# 06_ETHERNET.net
KiCad netlist of a schematic drawn in Altium Designer
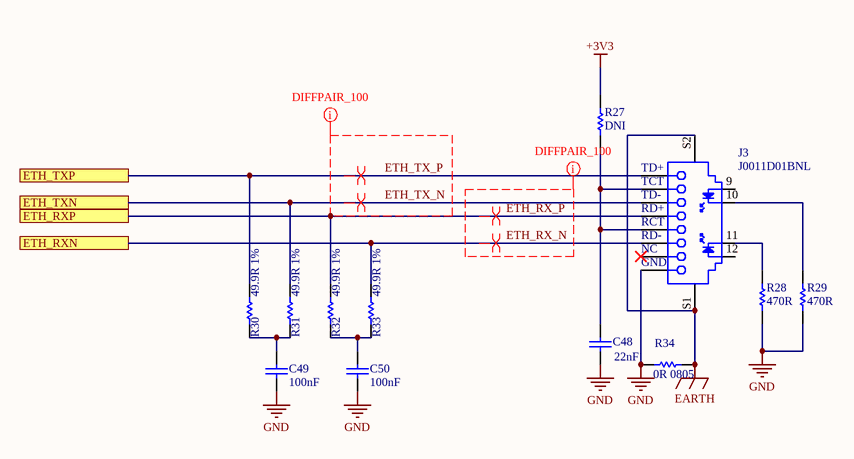
[diagram p0: 06. ETHERNET.SchDoc]

(export (version "E")
  (design (tool "Eeschema 10.0.6"))
  (components
    (comp (ref "C48")
      (value "22nF")
      (footprint "CAPC1005X60X30LL05T10")
      (fields (field (name "PART NUMBER") "GRM155R71H223KA12D") (field (name "MANUFACTURER") "Murata"))
      (libsource (lib "AM3358_DEV_BOARD") (part "CAP"))
    )
    (comp (ref "C49")
      (value "100nF")
      (footprint "CAPC1005X60X30LL05T10")
      (description "Chip Capacitor, 0.1 uF, +/- 10%, 16 V, -55 to 125 degC, 0402 (1005 Metric), RoHS, Tape and Reel")
      (fields (field (name "VOLTAGE") "16V") (field (name "TOLERANCE") "10%"))
      (libsource (lib "AM3358_DEV_BOARD") (part "CAP-NP-2"))
    )
    (comp (ref "C50")
      (value "100nF")
      (footprint "CAPC1005X60X30LL05T10")
      (description "Chip Capacitor, 0.1 uF, +/- 10%, 16 V, -55 to 125 degC, 0402 (1005 Metric), RoHS, Tape and Reel")
      (fields (field (name "VOLTAGE") "16V") (field (name "TOLERANCE") "10%"))
      (libsource (lib "AM3358_DEV_BOARD") (part "CAP-NP-2"))
    )
    (comp (ref "J3")
      (value "J0011D01BNL")
      (footprint "J0011D01BNL 1PORT 100 BASE-TX")
      (fields (field (name "MANUFACTURER") "Pulse Electronics"))
      (libsource (lib "AM3358_DEV_BOARD") (part "RJ45-12-2SHLD_F"))
    )
    (comp (ref "R27")
      (value "DNI")
      (footprint "RESC1005X40X25LL05T05")
      (fields (field (name "PART NUMBER") "CRCW040210R0FKEDHP") (field (name "MANUFACTURER") "Vishay Dale"))
      (libsource (lib "AM3358_DEV_BOARD") (part "RES"))
    )
    (comp (ref "R28")
      (value "470R")
      (footprint "RESC1005X40X25LL05T05")
      (fields (field (name "PART NUMBER") "CRCW0603470RFKEA") (field (name "MANUFACTURER") "Vishay Dale"))
      (libsource (lib "AM3358_DEV_BOARD") (part "RES"))
    )
    (comp (ref "R29")
      (value "470R")
      (footprint "RESC1005X40X25LL05T05")
      (fields (field (name "PART NUMBER") "CRCW0603470RFKEA") (field (name "MANUFACTURER") "Vishay Dale"))
      (libsource (lib "AM3358_DEV_BOARD") (part "RES"))
    )
    (comp (ref "R30")
      (value "49.9R 1%")
      (footprint "RESC1005X40X25LL05T05")
      (description "Precision Thick Film Chip Resistors")
      (fields (field (name "MANUFACTURER") "Panasonic") (field (name "PART NUMBER") "ERJ-2RKF49R9X"))
      (libsource (lib "AM3358_DEV_BOARD") (part "RES"))
    )
    (comp (ref "R31")
      (value "49.9R 1%")
      (footprint "RESC1005X40X25LL05T05")
      (description "Precision Thick Film Chip Resistors")
      (fields (field (name "MANUFACTURER") "Panasonic") (field (name "PART NUMBER") "ERJ-2RKF49R9X"))
      (libsource (lib "AM3358_DEV_BOARD") (part "RES"))
    )
    (comp (ref "R32")
      (value "49.9R 1%")
      (footprint "RESC1005X40X25LL05T05")
      (description "Precision Thick Film Chip Resistors")
      (fields (field (name "MANUFACTURER") "Panasonic") (field (name "PART NUMBER") "ERJ-2RKF49R9X"))
      (libsource (lib "AM3358_DEV_BOARD") (part "RES"))
    )
    (comp (ref "R33")
      (value "49.9R 1%")
      (footprint "RESC1005X40X25LL05T05")
      (description "Precision Thick Film Chip Resistors")
      (fields (field (name "MANUFACTURER") "Panasonic") (field (name "PART NUMBER") "ERJ-2RKF49R9X"))
      (libsource (lib "AM3358_DEV_BOARD") (part "RES"))
    )
    (comp (ref "R34")
      (value "0R 0805")
      (footprint "RESC2013X50X30LL20T20")
      (fields (field (name "MANUFACTURER") "Vishay Dale") (field (name "PART NUMBER") "CRCW08050000Z0EA"))
      (libsource (lib "Altium Content Vault") (part "RES"))
    )
  )
  (nets
    (net (code "1") (name "+3V3") (class "Default")
      (node (ref "R27") (pin "2") (pinfunction "2_2") (pintype "passive"))
    )
    (net (code "2") (name "/ETH_RX_N") (class "Default")
      (node (ref "J3") (pin "6") (pinfunction "RD-_6") (pintype "passive"))
      (node (ref "R33") (pin "2") (pinfunction "2_2") (pintype "passive"))
    )
    (net (code "3") (name "/ETH_RX_P") (class "Default")
      (node (ref "J3") (pin "4") (pinfunction "RD+_4") (pintype "passive"))
      (node (ref "R32") (pin "2") (pinfunction "2_2") (pintype "passive"))
    )
    (net (code "4") (name "/ETH_TX_N") (class "Default")
      (node (ref "J3") (pin "3") (pinfunction "TD-_3") (pintype "passive"))
      (node (ref "R31") (pin "2") (pinfunction "2_2") (pintype "passive"))
    )
    (net (code "5") (name "/ETH_TX_P") (class "Default")
      (node (ref "J3") (pin "1") (pinfunction "TD+_1") (pintype "passive"))
      (node (ref "R30") (pin "2") (pinfunction "2_2") (pintype "passive"))
    )
    (net (code "6") (name "EARTH") (class "Default")
      (node (ref "J3") (pin "S1") (pinfunction "S1_S1") (pintype "passive"))
      (node (ref "J3") (pin "S2") (pinfunction "S2_S2") (pintype "passive"))
      (node (ref "R34") (pin "2") (pinfunction "2_2") (pintype "passive"))
    )
    (net (code "7") (name "GND") (class "Default")
      (node (ref "C48") (pin "1") (pinfunction "1_1") (pintype "passive"))
      (node (ref "C49") (pin "1") (pinfunction "1_1") (pintype "passive"))
      (node (ref "C50") (pin "1") (pinfunction "1_1") (pintype "passive"))
      (node (ref "J3") (pin "8") (pinfunction "GND_8") (pintype "passive"))
      (node (ref "R28") (pin "1") (pinfunction "1_1") (pintype "passive"))
      (node (ref "R29") (pin "1") (pinfunction "1_1") (pintype "passive"))
      (node (ref "R34") (pin "1") (pinfunction "1_1") (pintype "passive"))
    )
    (net (code "8") (name "Net-(C49-Pad2)") (class "Default")
      (node (ref "C49") (pin "2") (pinfunction "2_2") (pintype "passive"))
      (node (ref "R30") (pin "1") (pinfunction "1_1") (pintype "passive"))
      (node (ref "R31") (pin "1") (pinfunction "1_1") (pintype "passive"))
    )
    (net (code "9") (name "Net-(C50-Pad2)") (class "Default")
      (node (ref "C50") (pin "2") (pinfunction "2_2") (pintype "passive"))
      (node (ref "R32") (pin "1") (pinfunction "1_1") (pintype "passive"))
      (node (ref "R33") (pin "1") (pinfunction "1_1") (pintype "passive"))
    )
    (net (code "10") (name "Net-(J3-Pad10)") (class "Default")
      (node (ref "J3") (pin "10") (pinfunction "10_10") (pintype "passive"))
      (node (ref "R29") (pin "2") (pinfunction "2_2") (pintype "passive"))
    )
    (net (code "11") (name "Net-(J3-Pad11)") (class "Default")
      (node (ref "J3") (pin "11") (pinfunction "11_11") (pintype "passive"))
      (node (ref "R28") (pin "2") (pinfunction "2_2") (pintype "passive"))
    )
    (net (code "12") (name "Net-(J3-RCT)") (class "Default")
      (node (ref "C48") (pin "2") (pinfunction "2_2") (pintype "passive"))
      (node (ref "J3") (pin "2") (pinfunction "TCT_2") (pintype "passive"))
      (node (ref "J3") (pin "5") (pinfunction "RCT_5") (pintype "passive"))
      (node (ref "R27") (pin "1") (pinfunction "1_1") (pintype "passive"))
    )
    (net (code "13") (name "unconnected-(J3-NC-Pad7)") (class "Default")
      (node (ref "J3") (pin "7") (pinfunction "NC_7") (pintype "passive+no_connect"))
    )
    (net (code "14") (name "unconnected-(J3-Pad9)") (class "Default")
      (node (ref "J3") (pin "9") (pinfunction "9_9") (pintype "passive"))
    )
    (net (code "15") (name "unconnected-(J3-Pad12)") (class "Default")
      (node (ref "J3") (pin "12") (pinfunction "12_12") (pintype "passive"))
    )
  )
)
